# Display.net
KiCad netlist of a schematic drawn in Altium Designer
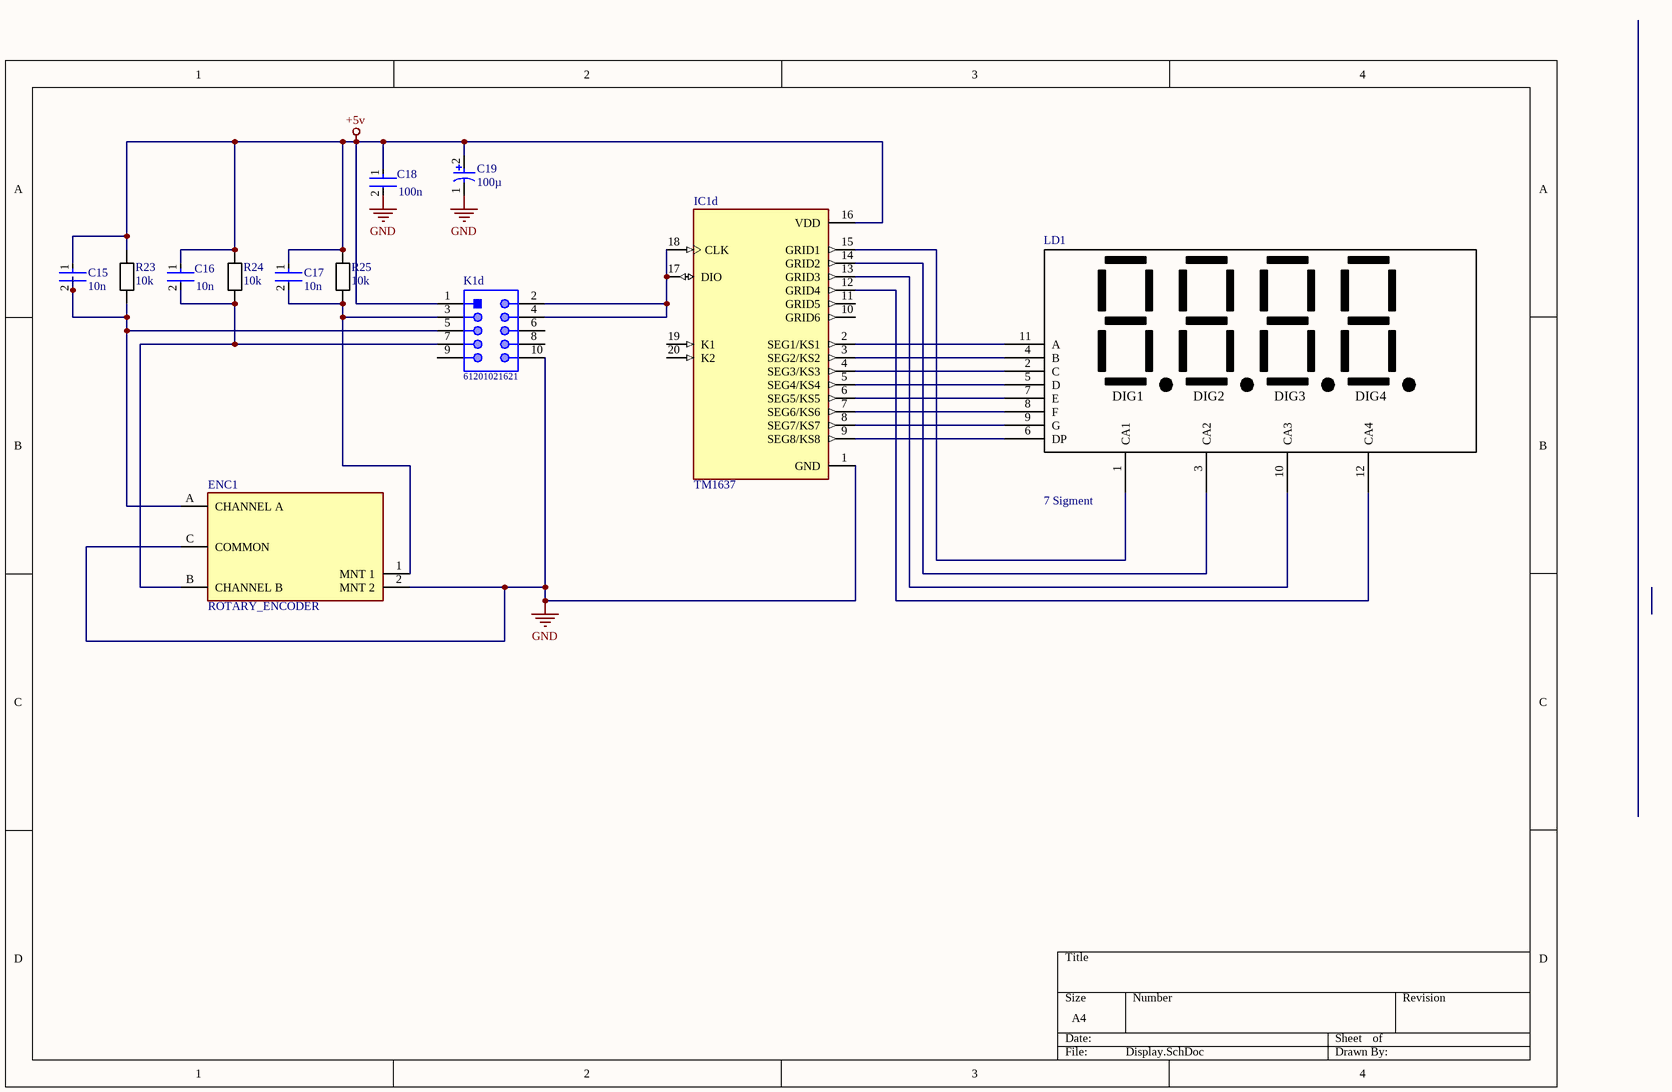
[diagram p0: Display.SchDoc]

(export (version "E")
  (design (tool "Eeschema 10.0.6"))
  (components
    (comp (ref "C15")
      (value "10n")
      (footprint "CC_0805_L")
      (fields
        (field (name "MANUFACTURER") "KEMET")
        (field (name "OCTOPART") "https://octopart.com/c0805c224k5ractu-kemet-144670")
        (field (name "MANUFACTURER PART NUMBER") "C0805C224K5RACTU")
      )
      (libsource (lib "Soldeerstation") (part "Capacitor_Ceramic"))
    )
    (comp (ref "C16")
      (value "10n")
      (footprint "CC_0805_L")
      (fields
        (field (name "MANUFACTURER") "KEMET")
        (field (name "OCTOPART") "https://octopart.com/c0805c224k5ractu-kemet-144670")
        (field (name "MANUFACTURER PART NUMBER") "C0805C224K5RACTU")
      )
      (libsource (lib "Soldeerstation") (part "Capacitor_Ceramic"))
    )
    (comp (ref "C17")
      (value "10n")
      (footprint "CC_0805_L")
      (fields
        (field (name "MANUFACTURER") "KEMET")
        (field (name "OCTOPART") "https://octopart.com/c0805c224k5ractu-kemet-144670")
        (field (name "MANUFACTURER PART NUMBER") "C0805C224K5RACTU")
      )
      (libsource (lib "Soldeerstation") (part "Capacitor_Ceramic"))
    )
    (comp (ref "C18")
      (value "100n")
      (footprint "CC_0805_L")
      (fields
        (field (name "MANUFACTURER") "KEMET")
        (field (name "OCTOPART") "https://octopart.com/c0805c224k5ractu-kemet-144670")
        (field (name "MANUFACTURER PART NUMBER") "C0805C224K5RACTU")
      )
      (libsource (lib "Soldeerstation") (part "Capacitor_Ceramic"))
    )
    (comp (ref "C19")
      (value "100µ")
      (footprint "CE_D8_L10")
      (fields (field (name "MANUFACTURER") "Panasonic"))
      (libsource (lib "Soldeerstation") (part "Capacitor_Electrolytic"))
    )
    (comp (ref "ENC1")
      (value "ROTARY_ENCODER")
      (footprint "PEC11R4225FN0024")
      (fields
        (field (name "MANUFACTURER PART NUMBER") "PEC11R-4015F-N0024")
        (field (name "MANUFACTURER") "Bourns")
        (field (name "OCTOPART") "https://octopart.com/pec11r-4015f-n0024-bourns-26648251")
      )
      (libsource (lib "Soldeerstation") (part "ROTARY_ENCODER"))
    )
    (comp (ref "IC1d")
      (value "TM1637")
      (footprint "SOP_20_M")
      (description "LED Drive Control Special Circuit")
      (fields (field (name "MF") "Titan Micro Electronics"))
      (libsource (lib "Soldeerstation") (part "TM1637"))
    )
    (comp (ref "K1d")
      (value "61201021621")
      (footprint "box header 10-pin")
      (description "Male Box Header WR-BHD, THT, Vertical, pitch 2.54 mm, 10 pins")
      (fields (field (name "MANUFACTURER") "Wurth Elektronik") (field (name "PUBLISHER") "WurthElektronik"))
      (libsource (lib "Soldeerstation") (part "Box Header"))
    )
    (comp (ref "LD1")
      (value "7 Sigment")
      (footprint "SamacSys:7-Sigment")
      (libsource (lib "Soldeerstation") (part "7 Sigment"))
    )
    (comp (ref "R23")
      (value "10k")
      (footprint "RESC2013X50X30ML20T20")
      (fields (field (name "MANUFACTURER") "Vishay Dale") (field (name "PART NUMBER") "CRCW08050000Z0EA"))
      (libsource (lib "Soldeerstation") (part "Weerstand"))
    )
    (comp (ref "R24")
      (value "10k")
      (footprint "RESC2013X50X30ML20T20")
      (fields (field (name "MANUFACTURER") "Vishay Dale") (field (name "PART NUMBER") "CRCW08050000Z0EA"))
      (libsource (lib "Soldeerstation") (part "Weerstand"))
    )
    (comp (ref "R25")
      (value "10k")
      (footprint "RESC2013X50X30ML20T20")
      (fields (field (name "MANUFACTURER") "Vishay Dale") (field (name "PART NUMBER") "CRCW08050000Z0EA"))
      (libsource (lib "Soldeerstation") (part "Weerstand"))
    )
  )
  (nets
    (net (code "1") (name "+5v") (class "Default")
      (node (ref "C15") (pin "1") (pinfunction "1_1") (pintype "passive"))
      (node (ref "C16") (pin "1") (pinfunction "1_1") (pintype "passive"))
      (node (ref "C17") (pin "1") (pinfunction "1_1") (pintype "passive"))
      (node (ref "C18") (pin "1") (pinfunction "1_1") (pintype "passive"))
      (node (ref "C19") (pin "2") (pinfunction "2_2") (pintype "passive"))
      (node (ref "IC1d") (pin "16") (pinfunction "VDD_16") (pintype "power_in"))
      (node (ref "K1d") (pin "1") (pinfunction "1_1") (pintype "passive"))
      (node (ref "R23") (pin "2") (pinfunction "2_2") (pintype "passive"))
      (node (ref "R24") (pin "2") (pinfunction "2_2") (pintype "passive"))
      (node (ref "R25") (pin "2") (pinfunction "2_2") (pintype "passive"))
    )
    (net (code "2") (name "GND") (class "Default")
      (node (ref "C18") (pin "2") (pinfunction "2_2") (pintype "passive"))
      (node (ref "C19") (pin "1") (pinfunction "1_1") (pintype "passive"))
      (node (ref "ENC1") (pin "2") (pinfunction "MNT_2_2") (pintype "passive"))
      (node (ref "ENC1") (pin "C") (pinfunction "COMMON_C") (pintype "passive"))
      (node (ref "IC1d") (pin "1") (pinfunction "GND_1") (pintype "power_in"))
      (node (ref "K1d") (pin "10") (pinfunction "10_10") (pintype "passive"))
    )
    (net (code "3") (name "Net-(ENC1-CHANNEL_A)") (class "Default")
      (node (ref "C15") (pin "2") (pinfunction "2_2") (pintype "passive"))
      (node (ref "ENC1") (pin "A") (pinfunction "CHANNEL_A_A") (pintype "passive"))
      (node (ref "K1d") (pin "5") (pinfunction "5_5") (pintype "passive"))
      (node (ref "R23") (pin "1") (pinfunction "1_1") (pintype "passive"))
    )
    (net (code "4") (name "Net-(ENC1-CHANNEL_B)") (class "Default")
      (node (ref "C16") (pin "2") (pinfunction "2_2") (pintype "passive"))
      (node (ref "ENC1") (pin "B") (pinfunction "CHANNEL_B_B") (pintype "passive"))
      (node (ref "K1d") (pin "7") (pinfunction "7_7") (pintype "passive"))
      (node (ref "R24") (pin "1") (pinfunction "1_1") (pintype "passive"))
    )
    (net (code "5") (name "Net-(ENC1-MNT_1)") (class "Default")
      (node (ref "C17") (pin "2") (pinfunction "2_2") (pintype "passive"))
      (node (ref "ENC1") (pin "1") (pinfunction "MNT_1_1") (pintype "passive"))
      (node (ref "K1d") (pin "3") (pinfunction "3_3") (pintype "passive"))
      (node (ref "R25") (pin "1") (pinfunction "1_1") (pintype "passive"))
    )
    (net (code "6") (name "Net-(IC1d-CLK)") (class "Default")
      (node (ref "IC1d") (pin "17") (pinfunction "DIO_17") (pintype "bidirectional"))
      (node (ref "IC1d") (pin "18") (pinfunction "CLK_18") (pintype "input"))
      (node (ref "K1d") (pin "2") (pinfunction "2_2") (pintype "passive"))
      (node (ref "K1d") (pin "4") (pinfunction "4_4") (pintype "passive"))
    )
    (net (code "7") (name "Net-(IC1d-GRID1)") (class "Default")
      (node (ref "IC1d") (pin "15") (pinfunction "GRID1_15") (pintype "output"))
      (node (ref "LD1") (pin "1") (pinfunction "CA1_1") (pintype "passive"))
    )
    (net (code "8") (name "Net-(IC1d-GRID2)") (class "Default")
      (node (ref "IC1d") (pin "14") (pinfunction "GRID2_14") (pintype "output"))
      (node (ref "LD1") (pin "3") (pinfunction "CA2_3") (pintype "passive"))
    )
    (net (code "9") (name "Net-(IC1d-GRID3)") (class "Default")
      (node (ref "IC1d") (pin "13") (pinfunction "GRID3_13") (pintype "output"))
      (node (ref "LD1") (pin "10") (pinfunction "CA3_10") (pintype "passive"))
    )
    (net (code "10") (name "Net-(IC1d-GRID4)") (class "Default")
      (node (ref "IC1d") (pin "12") (pinfunction "GRID4_12") (pintype "output"))
      (node (ref "LD1") (pin "12") (pinfunction "CA4_12") (pintype "passive"))
    )
    (net (code "11") (name "Net-(IC1d-SEG1{slash}KS1)") (class "Default")
      (node (ref "IC1d") (pin "2") (pinfunction "SEG1/KS1_2") (pintype "output"))
      (node (ref "LD1") (pin "11") (pinfunction "A_11") (pintype "passive"))
    )
    (net (code "12") (name "Net-(IC1d-SEG2{slash}KS2)") (class "Default")
      (node (ref "IC1d") (pin "3") (pinfunction "SEG2/KS2_3") (pintype "output"))
      (node (ref "LD1") (pin "4") (pinfunction "B_4") (pintype "passive"))
    )
    (net (code "13") (name "Net-(IC1d-SEG3{slash}KS3)") (class "Default")
      (node (ref "IC1d") (pin "4") (pinfunction "SEG3/KS3_4") (pintype "output"))
      (node (ref "LD1") (pin "2") (pinfunction "C_2") (pintype "passive"))
    )
    (net (code "14") (name "Net-(IC1d-SEG4{slash}KS4)") (class "Default")
      (node (ref "IC1d") (pin "5") (pinfunction "SEG4/KS4_5") (pintype "output"))
      (node (ref "LD1") (pin "5") (pinfunction "D_5") (pintype "passive"))
    )
    (net (code "15") (name "Net-(IC1d-SEG5{slash}KS5)") (class "Default")
      (node (ref "IC1d") (pin "6") (pinfunction "SEG5/KS5_6") (pintype "output"))
      (node (ref "LD1") (pin "7") (pinfunction "E_7") (pintype "passive"))
    )
    (net (code "16") (name "Net-(IC1d-SEG6{slash}KS6)") (class "Default")
      (node (ref "IC1d") (pin "7") (pinfunction "SEG6/KS6_7") (pintype "output"))
      (node (ref "LD1") (pin "8") (pinfunction "F_8") (pintype "passive"))
    )
    (net (code "17") (name "Net-(IC1d-SEG7{slash}KS7)") (class "Default")
      (node (ref "IC1d") (pin "8") (pinfunction "SEG7/KS7_8") (pintype "output"))
      (node (ref "LD1") (pin "9") (pinfunction "G_9") (pintype "passive"))
    )
    (net (code "18") (name "Net-(IC1d-SEG8{slash}KS8)") (class "Default")
      (node (ref "IC1d") (pin "9") (pinfunction "SEG8/KS8_9") (pintype "output"))
      (node (ref "LD1") (pin "6") (pinfunction "DP_6") (pintype "passive"))
    )
    (net (code "19") (name "unconnected-(IC1d-GRID5-Pad11)") (class "Default")
      (node (ref "IC1d") (pin "11") (pinfunction "GRID5_11") (pintype "output"))
    )
    (net (code "20") (name "unconnected-(IC1d-GRID6-Pad10)") (class "Default")
      (node (ref "IC1d") (pin "10") (pinfunction "GRID6_10") (pintype "output"))
    )
    (net (code "21") (name "unconnected-(IC1d-K1-Pad19)") (class "Default")
      (node (ref "IC1d") (pin "19") (pinfunction "K1_19") (pintype "input"))
    )
    (net (code "22") (name "unconnected-(IC1d-K2-Pad20)") (class "Default")
      (node (ref "IC1d") (pin "20") (pinfunction "K2_20") (pintype "input"))
    )
    (net (code "23") (name "unconnected-(K1d-Pad6)") (class "Default")
      (node (ref "K1d") (pin "6") (pinfunction "6_6") (pintype "passive"))
    )
    (net (code "24") (name "unconnected-(K1d-Pad8)") (class "Default")
      (node (ref "K1d") (pin "8") (pinfunction "8_8") (pintype "passive"))
    )
    (net (code "25") (name "unconnected-(K1d-Pad9)") (class "Default")
      (node (ref "K1d") (pin "9") (pinfunction "9_9") (pintype "passive"))
    )
  )
)
